# SH6_-_LOAD_MONITORING_2.net
KiCad netlist of a schematic drawn in Altium Designer
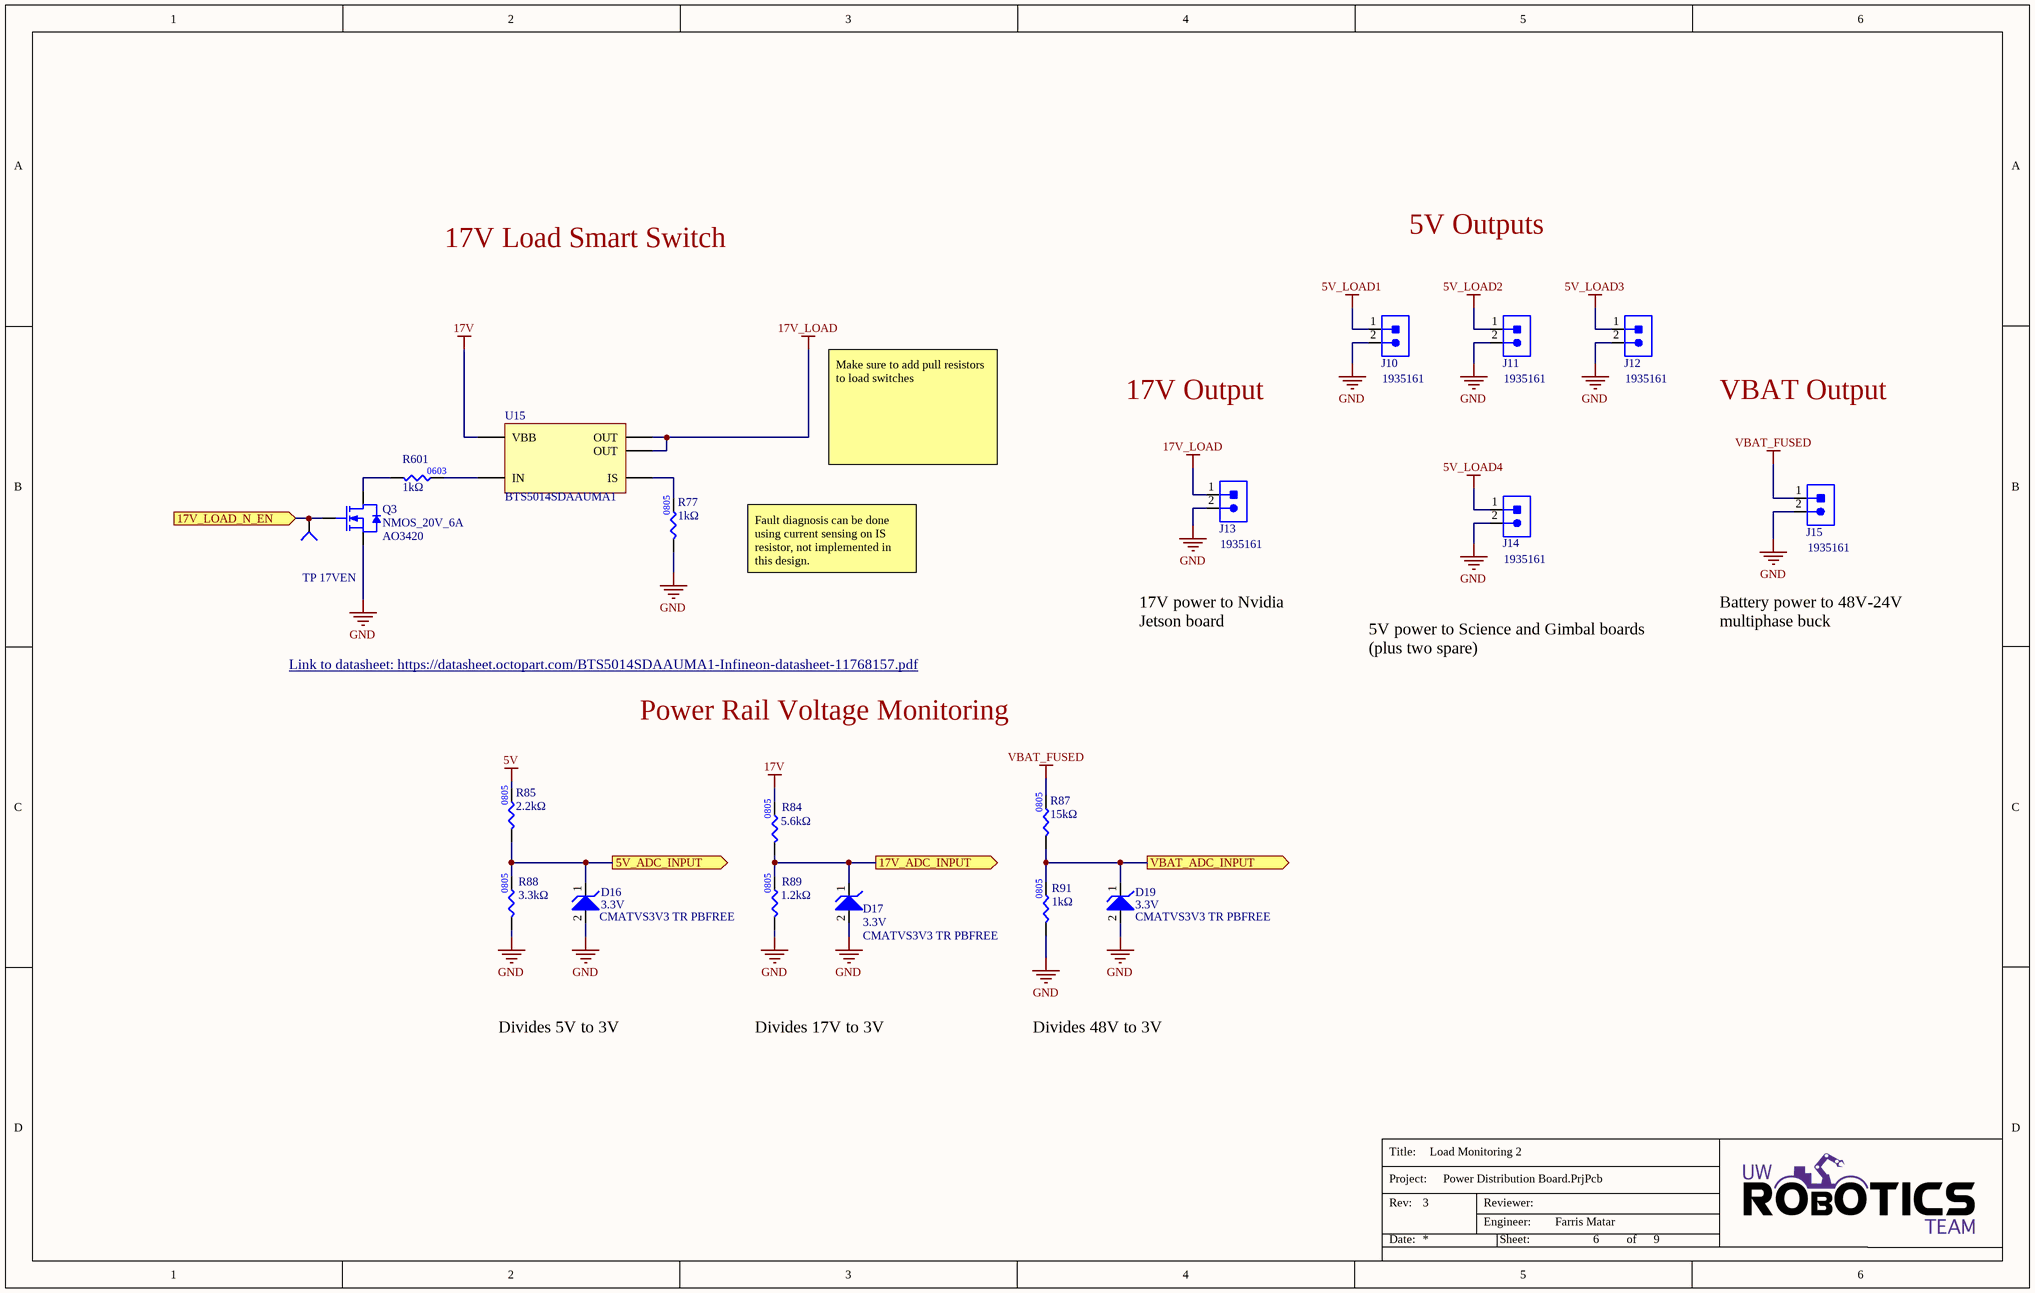
[diagram p0: SH6 - LOAD MONITORING 2.SchDoc]

(export (version "E")
  (design (tool "Eeschema 10.0.6"))
  (components
    (comp (ref "D16")
      (value "TVS_DIODE_UNIDIR_3.3V_7A")
      (footprint "SOD-923")
      (description "TVS DIODE 3.3VWM 11VC SOD923")
      (fields
        (field (name "MANUFACTURER PART NUMBER 1") "CMATVS3V3 TR PBFREE")
        (field (name "VOLTAGE - REVERSE STANDOFF (TYP)") "3.3V")
      )
      (libsource (lib "UWRT_Schematic_Library_2020") (part "TVS_DIODE_UNIDIR_3.3V_7A"))
    )
    (comp (ref "D17")
      (value "TVS_DIODE_UNIDIR_3.3V_7A")
      (footprint "SOD-923")
      (description "TVS DIODE 3.3VWM 11VC SOD923")
      (fields
        (field (name "MANUFACTURER PART NUMBER 1") "CMATVS3V3 TR PBFREE")
        (field (name "VOLTAGE - REVERSE STANDOFF (TYP)") "3.3V")
      )
      (libsource (lib "UWRT_Schematic_Library_2020") (part "TVS_DIODE_UNIDIR_3.3V_7A"))
    )
    (comp (ref "D19")
      (value "TVS_DIODE_UNIDIR_3.3V_7A")
      (footprint "SOD-923")
      (description "TVS DIODE 3.3VWM 11VC SOD923")
      (fields
        (field (name "MANUFACTURER PART NUMBER 1") "CMATVS3V3 TR PBFREE")
        (field (name "VOLTAGE - REVERSE STANDOFF (TYP)") "3.3V")
      )
      (libsource (lib "UWRT_Schematic_Library_2020") (part "TVS_DIODE_UNIDIR_3.3V_7A"))
    )
    (comp (ref "J10")
      (value "CON_2M_TERM")
      (footprint "1935161")
      (description "TERM BLK 2POS SIDE ENTRY 5MM")
      (fields (field (name "VOLTAGE") "300V") (field (name "MANUFACTURER PART NUMBER 1") "1935161"))
      (libsource (lib "UWRT_Schematic_Library_2020") (part "CON_2M_TERM"))
    )
    (comp (ref "J11")
      (value "CON_2M_TERM")
      (footprint "1935161")
      (description "TERM BLK 2POS SIDE ENTRY 5MM")
      (fields (field (name "VOLTAGE") "300V") (field (name "MANUFACTURER PART NUMBER 1") "1935161"))
      (libsource (lib "UWRT_Schematic_Library_2020") (part "CON_2M_TERM"))
    )
    (comp (ref "J12")
      (value "CON_2M_TERM")
      (footprint "1935161")
      (description "TERM BLK 2POS SIDE ENTRY 5MM")
      (fields (field (name "VOLTAGE") "300V") (field (name "MANUFACTURER PART NUMBER 1") "1935161"))
      (libsource (lib "UWRT_Schematic_Library_2020") (part "CON_2M_TERM"))
    )
    (comp (ref "J13")
      (value "CON_2M_TERM")
      (footprint "1935161")
      (description "TERM BLK 2POS SIDE ENTRY 5MM")
      (fields (field (name "VOLTAGE") "300V") (field (name "MANUFACTURER PART NUMBER 1") "1935161"))
      (libsource (lib "UWRT_Schematic_Library_2020") (part "CON_2M_TERM"))
    )
    (comp (ref "J14")
      (value "CON_2M_TERM")
      (footprint "1935161")
      (description "TERM BLK 2POS SIDE ENTRY 5MM")
      (fields (field (name "VOLTAGE") "300V") (field (name "MANUFACTURER PART NUMBER 1") "1935161"))
      (libsource (lib "UWRT_Schematic_Library_2020") (part "CON_2M_TERM"))
    )
    (comp (ref "J15")
      (value "CON_2M_TERM")
      (footprint "1935161")
      (description "TERM BLK 2POS SIDE ENTRY 5MM")
      (fields (field (name "VOLTAGE") "300V") (field (name "MANUFACTURER PART NUMBER 1") "1935161"))
      (libsource (lib "UWRT_Schematic_Library_2020") (part "CON_2M_TERM"))
    )
    (comp (ref "Q3")
      (value "NMOS_20V_6A")
      (footprint "SOT23-3")
      (description "MOSFET N-CH 20V 6A SOT-23")
      (fields (field (name "MANUFACTURER PART NUMBER 1") "AO3420"))
      (libsource (lib "UWRT_Schematic_Library_2020") (part "NMOS_20V_6A"))
    )
    (comp (ref "R77")
      (value "1kΩ")
      (footprint "RES0805")
      (description "RES 1K OHM 1% 1/8W 0805")
      (fields (field (name "LCSC PART #") "C17513") (field (name "Comment") "RES_1kΩ_0805_1%"))
      (libsource (lib "UWRT_Schematic_Library_2020") (part "RES_1kΩ_0805_1%"))
    )
    (comp (ref "R84")
      (value "5.6kΩ")
      (footprint "RES0805")
      (description "RES 5.6K OHM 5% 1/8W 0805")
      (fields (field (name "TOLERANCE") "5%") (field (name "Comment") "RES_5.6kΩ_0805"))
      (libsource (lib "UWRT_Schematic_Library_2020") (part "RES_5.6kΩ_0805_5%"))
    )
    (comp (ref "R85")
      (value "2.2kΩ")
      (footprint "RES0805")
      (description "RES 2.2K OHM 5% 1/8W 0805")
      (fields (field (name "TOLERANCE") "5%") (field (name "Comment") "RES_2.2kΩ_0805"))
      (libsource (lib "UWRT_Schematic_Library_2020") (part "RES_2.2kΩ_0805_5%"))
    )
    (comp (ref "R87")
      (value "15kΩ")
      (footprint "RES0805")
      (description "RES 15K OHM 1% 1/8W 0805")
      (fields (field (name "Comment") "RES_15kΩ_0805_1%"))
      (libsource (lib "UWRT_Schematic_Library_2020") (part "RES_15kΩ_0805_1%"))
    )
    (comp (ref "R88")
      (value "3.3kΩ")
      (footprint "RES0805")
      (description "RES 3.3K OHM 1% 1/8W 0805")
      (fields (field (name "LCSC PART #") "C26010") (field (name "Comment") "RES_3.3kΩ_0805_1%"))
      (libsource (lib "UWRT_Schematic_Library_2020") (part "RES_3.3kΩ_0805_1%"))
    )
    (comp (ref "R89")
      (value "1.2kΩ")
      (footprint "RES0805")
      (description "RES 1.2K OHM 5% 1/8W 0805")
      (fields (field (name "TOLERANCE") "5%") (field (name "Comment") "RES_1.2kΩ_0805"))
      (libsource (lib "UWRT_Schematic_Library_2020") (part "RES_1.2kΩ_0805_5%"))
    )
    (comp (ref "R91")
      (value "1kΩ")
      (footprint "RES0805")
      (description "RES 1K OHM 1% 1/8W 0805")
      (fields (field (name "LCSC PART #") "C17513") (field (name "Comment") "RES_1kΩ_0805_1%_1"))
      (libsource (lib "UWRT_Schematic_Library_2020") (part "RES_1kΩ_0805_1%_1"))
    )
    (comp (ref "R601")
      (value "1kΩ")
      (footprint "RES0603")
      (description "RES 1K OHM 5% 1/10W 0603")
      (fields (field (name "Comment") "RES_1kΩ_0603_5%"))
      (libsource (lib "UWRT_Schematic_Library_2020") (part "RES_1kΩ_0603_5%"))
    )
    (comp (ref "TP 17VEN")
      (value "TESTPOINT_1MM_CIRCLE")
      (footprint "TESTPOINT_CIRCLE_1MM")
      (description "TESTPOINT 1MM CIRCLE")
      (libsource (lib "UWRT_Schematic_Library_2020") (part "TESTPOINT_1MM_CIRCLE"))
    )
    (comp (ref "U15")
      (value "BTS5014SDAAUMA1")
      (footprint "D2PAK-4")
      (description "IC PWR SWITCH N-CHAN 1:1 TO252-5")
      (fields (field (name "MANUFACTURER PART NUMBER 1") "BTS5014SDAAUMA1"))
      (libsource (lib "UWRT_Schematic_Library_2020") (part "BTS5014SDAAUMA1"))
    )
  )
  (nets
    (net (code "1") (name "/5V_ADC_INPUT") (class "Default")
      (node (ref "D16") (pin "1") (pinfunction "1_1") (pintype "passive"))
      (node (ref "R85") (pin "1") (pinfunction "1_1") (pintype "passive"))
      (node (ref "R88") (pin "2") (pinfunction "2_2") (pintype "passive"))
    )
    (net (code "2") (name "/17V_ADC_INPUT") (class "Default")
      (node (ref "D17") (pin "1") (pinfunction "1_1") (pintype "passive"))
      (node (ref "R84") (pin "1") (pinfunction "1_1") (pintype "passive"))
      (node (ref "R89") (pin "2") (pinfunction "2_2") (pintype "passive"))
    )
    (net (code "3") (name "/17V_LOAD_N_EN") (class "Default")
      (node (ref "Q3") (pin "1") (pinfunction "GATE_1") (pintype "passive"))
      (node (ref "TP 17VEN") (pin "1") (pinfunction "=value_1") (pintype "passive"))
    )
    (net (code "4") (name "/VBAT_ADC_INPUT") (class "Default")
      (node (ref "D19") (pin "1") (pinfunction "1_1") (pintype "passive"))
      (node (ref "R87") (pin "1") (pinfunction "1_1") (pintype "passive"))
      (node (ref "R91") (pin "2") (pinfunction "2_2") (pintype "passive"))
    )
    (net (code "5") (name "5V") (class "Default")
      (node (ref "R85") (pin "2") (pinfunction "2_2") (pintype "passive"))
    )
    (net (code "6") (name "5V_LOAD1") (class "Default")
      (node (ref "J10") (pin "1") (pinfunction "1_1") (pintype "passive"))
    )
    (net (code "7") (name "5V_LOAD2") (class "Default")
      (node (ref "J11") (pin "1") (pinfunction "1_1") (pintype "passive"))
    )
    (net (code "8") (name "5V_LOAD3") (class "Default")
      (node (ref "J12") (pin "1") (pinfunction "1_1") (pintype "passive"))
    )
    (net (code "9") (name "5V_LOAD4") (class "Default")
      (node (ref "J14") (pin "1") (pinfunction "1_1") (pintype "passive"))
    )
    (net (code "10") (name "17V") (class "Default")
      (node (ref "R84") (pin "2") (pinfunction "2_2") (pintype "passive"))
      (node (ref "U15") (pin "3") (pinfunction "VBB_3") (pintype "passive"))
    )
    (net (code "11") (name "17V_LOAD") (class "Default")
      (node (ref "J13") (pin "1") (pinfunction "1_1") (pintype "passive"))
      (node (ref "U15") (pin "1") (pinfunction "OUT_1") (pintype "passive"))
      (node (ref "U15") (pin "5") (pinfunction "OUT_5") (pintype "passive"))
    )
    (net (code "12") (name "GND") (class "Default")
      (node (ref "D16") (pin "2") (pinfunction "2_2") (pintype "passive"))
      (node (ref "D17") (pin "2") (pinfunction "2_2") (pintype "passive"))
      (node (ref "D19") (pin "2") (pinfunction "2_2") (pintype "passive"))
      (node (ref "J10") (pin "2") (pinfunction "2_2") (pintype "passive"))
      (node (ref "J11") (pin "2") (pinfunction "2_2") (pintype "passive"))
      (node (ref "J12") (pin "2") (pinfunction "2_2") (pintype "passive"))
      (node (ref "J13") (pin "2") (pinfunction "2_2") (pintype "passive"))
      (node (ref "J14") (pin "2") (pinfunction "2_2") (pintype "passive"))
      (node (ref "J15") (pin "2") (pinfunction "2_2") (pintype "passive"))
      (node (ref "Q3") (pin "2") (pinfunction "SOURCE_2") (pintype "passive"))
      (node (ref "R77") (pin "1") (pinfunction "1_1") (pintype "passive"))
      (node (ref "R88") (pin "1") (pinfunction "1_1") (pintype "passive"))
      (node (ref "R89") (pin "1") (pinfunction "1_1") (pintype "passive"))
      (node (ref "R91") (pin "1") (pinfunction "1_1") (pintype "passive"))
    )
    (net (code "13") (name "Net-(Q3-DRAIN)") (class "Default")
      (node (ref "Q3") (pin "3") (pinfunction "DRAIN_3") (pintype "passive"))
      (node (ref "R601") (pin "1") (pinfunction "1_1") (pintype "passive"))
    )
    (net (code "14") (name "Net-(U15-IN)") (class "Default")
      (node (ref "R601") (pin "2") (pinfunction "2_2") (pintype "passive"))
      (node (ref "U15") (pin "2") (pinfunction "IN_2") (pintype "passive"))
    )
    (net (code "15") (name "Net-(U15-IS)") (class "Default")
      (node (ref "R77") (pin "2") (pinfunction "2_2") (pintype "passive"))
      (node (ref "U15") (pin "4") (pinfunction "IS_4") (pintype "passive"))
    )
    (net (code "16") (name "VBAT_FUSED") (class "Default")
      (node (ref "J15") (pin "1") (pinfunction "1_1") (pintype "passive"))
      (node (ref "R87") (pin "2") (pinfunction "2_2") (pintype "passive"))
    )
  )
)
